# i2c_adc_avr_inline_soic_pth.net
KiCad netlist of a schematic drawn in EAGLE
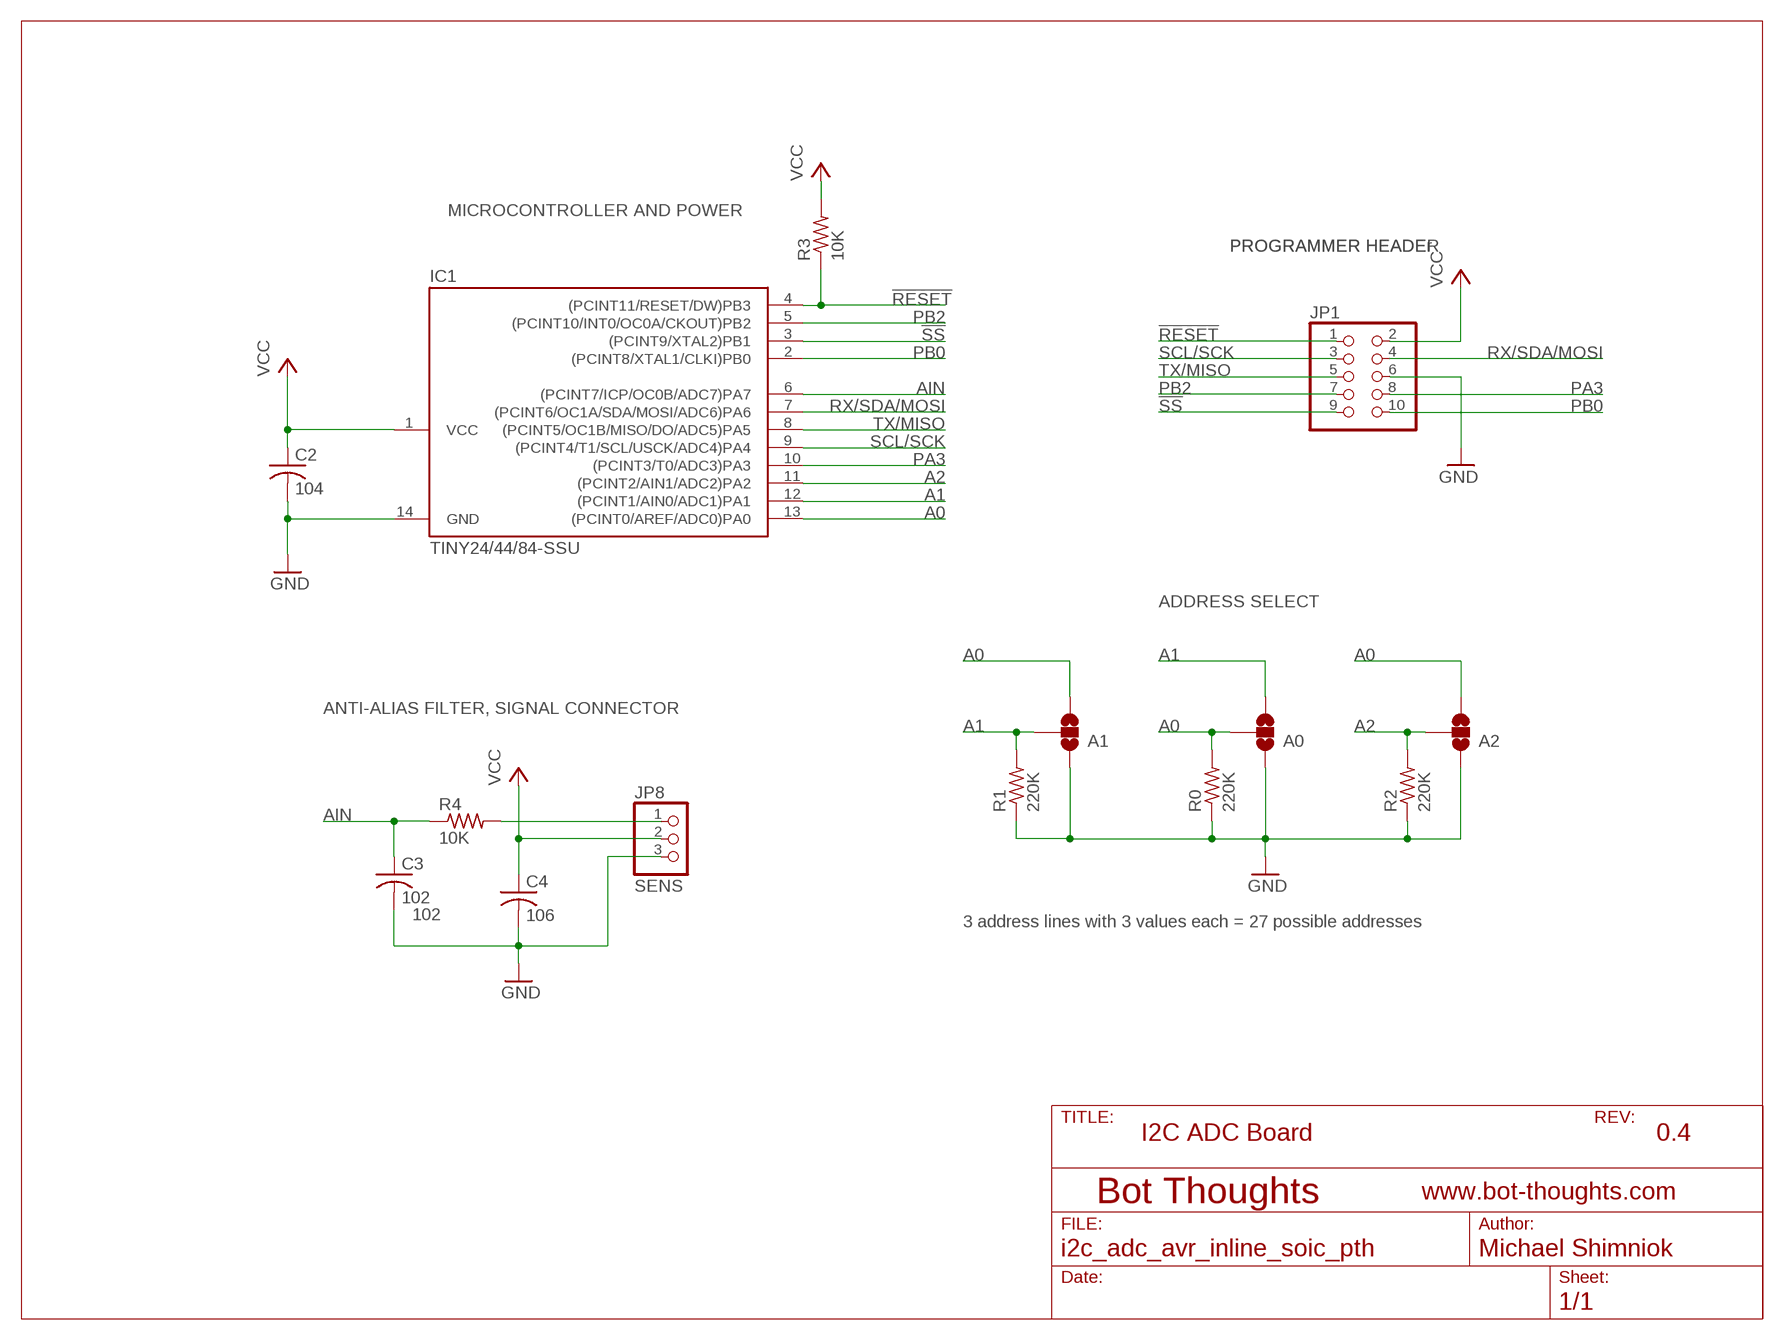
[diagram p0: schematic, sheet 1]

(export (version "E")
  (design (tool "Eeschema 10.0.6"))
  (components
    (comp (ref "A0")
      (value "SOLDERJUMPER_2WAYS")
      (footprint "eagle-import:SJ_3")
      (libsource (lib "eagle-import") (part "SOLDERJUMPER_2WAYS"))
    )
    (comp (ref "A1")
      (value "SOLDERJUMPER_2WAYS")
      (footprint "eagle-import:SJ_3")
      (libsource (lib "eagle-import") (part "SOLDERJUMPER_2WAYS"))
    )
    (comp (ref "A2")
      (value "SOLDERJUMPER_2WAYS")
      (footprint "eagle-import:SJ_3")
      (libsource (lib "eagle-import") (part "SOLDERJUMPER_2WAYS"))
    )
    (comp (ref "C2")
      (value "104")
      (footprint "eagle-import:C0603")
      (fields (field (name "PARTNO") "C1608X7R1E104K080AA"))
      (libsource (lib "eagle-import") (part "C-USC0603"))
    )
    (comp (ref "C3")
      (value "102")
      (footprint "eagle-import:C0603")
      (fields (field (name "CODE") "102") (field (name "PARTNO") "CL10B102KB8SFNC"))
      (libsource (lib "eagle-import") (part "C-USC0603"))
    )
    (comp (ref "C4")
      (value "106")
      (footprint "eagle-import:C0603")
      (fields (field (name "PARTNO") "CL10A106MP8NNNC"))
      (libsource (lib "eagle-import") (part "C-USC0603"))
    )
    (comp (ref "IC1")
      (value "TINY24/44/84-SSU")
      (footprint "eagle-import:SOIC14")
      (libsource (lib "eagle-import") (part "TINY24/44/84-SSU"))
    )
    (comp (ref "JP1")
      (value "PINHD-2X05_2.54-90°")
      (footprint "eagle-import:2X05_90")
      (libsource (lib "eagle-import") (part "PINHD-2X05_2.54-90°"))
    )
    (comp (ref "JP8")
      (value "SENS")
      (footprint "eagle-import:1X03-S")
      (libsource (lib "eagle-import") (part "PINHD-1X03_2.54-S"))
    )
    (comp (ref "R0")
      (value "220K")
      (footprint "eagle-import:R0603")
      (fields (field (name "PARTNO") "RC1608J224CS"))
      (libsource (lib "eagle-import") (part "R-US_R0603"))
    )
    (comp (ref "R1")
      (value "220K")
      (footprint "eagle-import:R0603")
      (fields (field (name "PARTNO") "RC1608J224CS"))
      (libsource (lib "eagle-import") (part "R-US_R0603"))
    )
    (comp (ref "R2")
      (value "220K")
      (footprint "eagle-import:R0603")
      (fields (field (name "PARTNO") "RC1608J224CS"))
      (libsource (lib "eagle-import") (part "R-US_R0603"))
    )
    (comp (ref "R3")
      (value "10K")
      (footprint "eagle-import:R0603")
      (fields (field (name "PARTNO") "1622829-1"))
      (libsource (lib "eagle-import") (part "R-US_R0603"))
    )
    (comp (ref "R4")
      (value "10K")
      (footprint "eagle-import:R0603")
      (fields (field (name "PARTNO") "1622829-1"))
      (libsource (lib "eagle-import") (part "R-US_R0603"))
    )
  )
  (nets
    (net (code "1") (name "/A0") (class "Default")
      (node (ref "A0") (pin "2") (pinfunction "2_2") (pintype "passive"))
      (node (ref "A1") (pin "3") (pinfunction "3_3") (pintype "passive"))
      (node (ref "A2") (pin "3") (pinfunction "3_3") (pintype "passive"))
      (node (ref "IC1") (pin "13") (pinfunction "(PCINT0/AREF/ADC0)PA0_13") (pintype "bidirectional"))
      (node (ref "R0") (pin "2") (pinfunction "2_2") (pintype "passive"))
    )
    (net (code "2") (name "/A1") (class "Default")
      (node (ref "A0") (pin "3") (pinfunction "3_3") (pintype "passive"))
      (node (ref "A1") (pin "2") (pinfunction "2_2") (pintype "passive"))
      (node (ref "IC1") (pin "12") (pinfunction "(PCINT1/AIN0/ADC1)PA1_12") (pintype "bidirectional"))
      (node (ref "R1") (pin "2") (pinfunction "2_2") (pintype "passive"))
    )
    (net (code "3") (name "/A2") (class "Default")
      (node (ref "A2") (pin "2") (pinfunction "2_2") (pintype "passive"))
      (node (ref "IC1") (pin "11") (pinfunction "(PCINT2/AIN1/ADC2)PA2_11") (pintype "bidirectional"))
      (node (ref "R2") (pin "2") (pinfunction "2_2") (pintype "passive"))
    )
    (net (code "4") (name "/AIN") (class "Default")
      (node (ref "C3") (pin "1") (pinfunction "1_1") (pintype "passive"))
      (node (ref "IC1") (pin "6") (pinfunction "(PCINT7/ICP/OC0B/ADC7)PA7_6") (pintype "bidirectional"))
      (node (ref "R4") (pin "1") (pinfunction "1_1") (pintype "passive"))
    )
    (net (code "5") (name "/PA3") (class "Default")
      (node (ref "IC1") (pin "10") (pinfunction "(PCINT3/T0/ADC3)PA3_10") (pintype "bidirectional"))
      (node (ref "JP1") (pin "8") (pinfunction "8_8") (pintype "passive"))
    )
    (net (code "6") (name "/PB0") (class "Default")
      (node (ref "IC1") (pin "2") (pinfunction "(PCINT8/XTAL1/CLKI)PB0_2") (pintype "bidirectional"))
      (node (ref "JP1") (pin "10") (pinfunction "10_10") (pintype "passive"))
    )
    (net (code "7") (name "/PB2") (class "Default")
      (node (ref "IC1") (pin "5") (pinfunction "(PCINT10/INT0/OC0A/CKOUT)PB2_5") (pintype "bidirectional"))
      (node (ref "JP1") (pin "7") (pinfunction "7_7") (pintype "passive"))
    )
    (net (code "8") (name "/RX{slash}SDA{slash}MOSI") (class "Default")
      (node (ref "IC1") (pin "7") (pinfunction "(PCINT6/OC1A/SDA/MOSI/ADC6)PA6_7") (pintype "bidirectional"))
      (node (ref "JP1") (pin "4") (pinfunction "4_4") (pintype "passive"))
    )
    (net (code "9") (name "/SCL{slash}SCK") (class "Default")
      (node (ref "IC1") (pin "9") (pinfunction "(PCINT4/T1/SCL/USCK/ADC4)PA4_9") (pintype "bidirectional"))
      (node (ref "JP1") (pin "3") (pinfunction "3_3") (pintype "passive"))
    )
    (net (code "10") (name "/TX{slash}MISO") (class "Default")
      (node (ref "IC1") (pin "8") (pinfunction "(PCINT5/OC1B/MISO/DO/ADC5)PA5_8") (pintype "bidirectional"))
      (node (ref "JP1") (pin "5") (pinfunction "5_5") (pintype "passive"))
    )
    (net (code "11") (name "/~{RESET}") (class "Default")
      (node (ref "IC1") (pin "4") (pinfunction "(PCINT11/RESET/DW)PB3_4") (pintype "bidirectional"))
      (node (ref "JP1") (pin "1") (pinfunction "1_1") (pintype "passive"))
      (node (ref "R3") (pin "1") (pinfunction "1_1") (pintype "passive"))
    )
    (net (code "12") (name "/~{SS}") (class "Default")
      (node (ref "IC1") (pin "3") (pinfunction "(PCINT9/XTAL2)PB1_3") (pintype "bidirectional"))
      (node (ref "JP1") (pin "9") (pinfunction "9_9") (pintype "passive"))
    )
    (net (code "13") (name "GND") (class "Default")
      (node (ref "A0") (pin "1") (pinfunction "1_1") (pintype "passive"))
      (node (ref "A1") (pin "1") (pinfunction "1_1") (pintype "passive"))
      (node (ref "A2") (pin "1") (pinfunction "1_1") (pintype "passive"))
      (node (ref "C2") (pin "2") (pinfunction "2_2") (pintype "passive"))
      (node (ref "C3") (pin "2") (pinfunction "2_2") (pintype "passive"))
      (node (ref "C4") (pin "2") (pinfunction "2_2") (pintype "passive"))
      (node (ref "IC1") (pin "14") (pinfunction "GND_14") (pintype "power_in"))
      (node (ref "JP1") (pin "6") (pinfunction "6_6") (pintype "passive"))
      (node (ref "JP8") (pin "3") (pinfunction "3_3") (pintype "passive"))
      (node (ref "R0") (pin "1") (pinfunction "1_1") (pintype "passive"))
      (node (ref "R1") (pin "1") (pinfunction "1_1") (pintype "passive"))
      (node (ref "R2") (pin "1") (pinfunction "1_1") (pintype "passive"))
    )
    (net (code "14") (name "Net-(JP8-Pad1)") (class "Default")
      (node (ref "JP8") (pin "1") (pinfunction "1_1") (pintype "passive"))
      (node (ref "R4") (pin "2") (pinfunction "2_2") (pintype "passive"))
    )
    (net (code "15") (name "VCC") (class "Default")
      (node (ref "C2") (pin "1") (pinfunction "1_1") (pintype "passive"))
      (node (ref "C4") (pin "1") (pinfunction "1_1") (pintype "passive"))
      (node (ref "IC1") (pin "1") (pinfunction "VCC_1") (pintype "power_in"))
      (node (ref "JP1") (pin "2") (pinfunction "2_2") (pintype "passive"))
      (node (ref "JP8") (pin "2") (pinfunction "2_2") (pintype "passive"))
      (node (ref "R3") (pin "2") (pinfunction "2_2") (pintype "passive"))
    )
  )
)
